# GEN_CART_EPROM_only.net
KiCad netlist of a schematic drawn in EAGLE
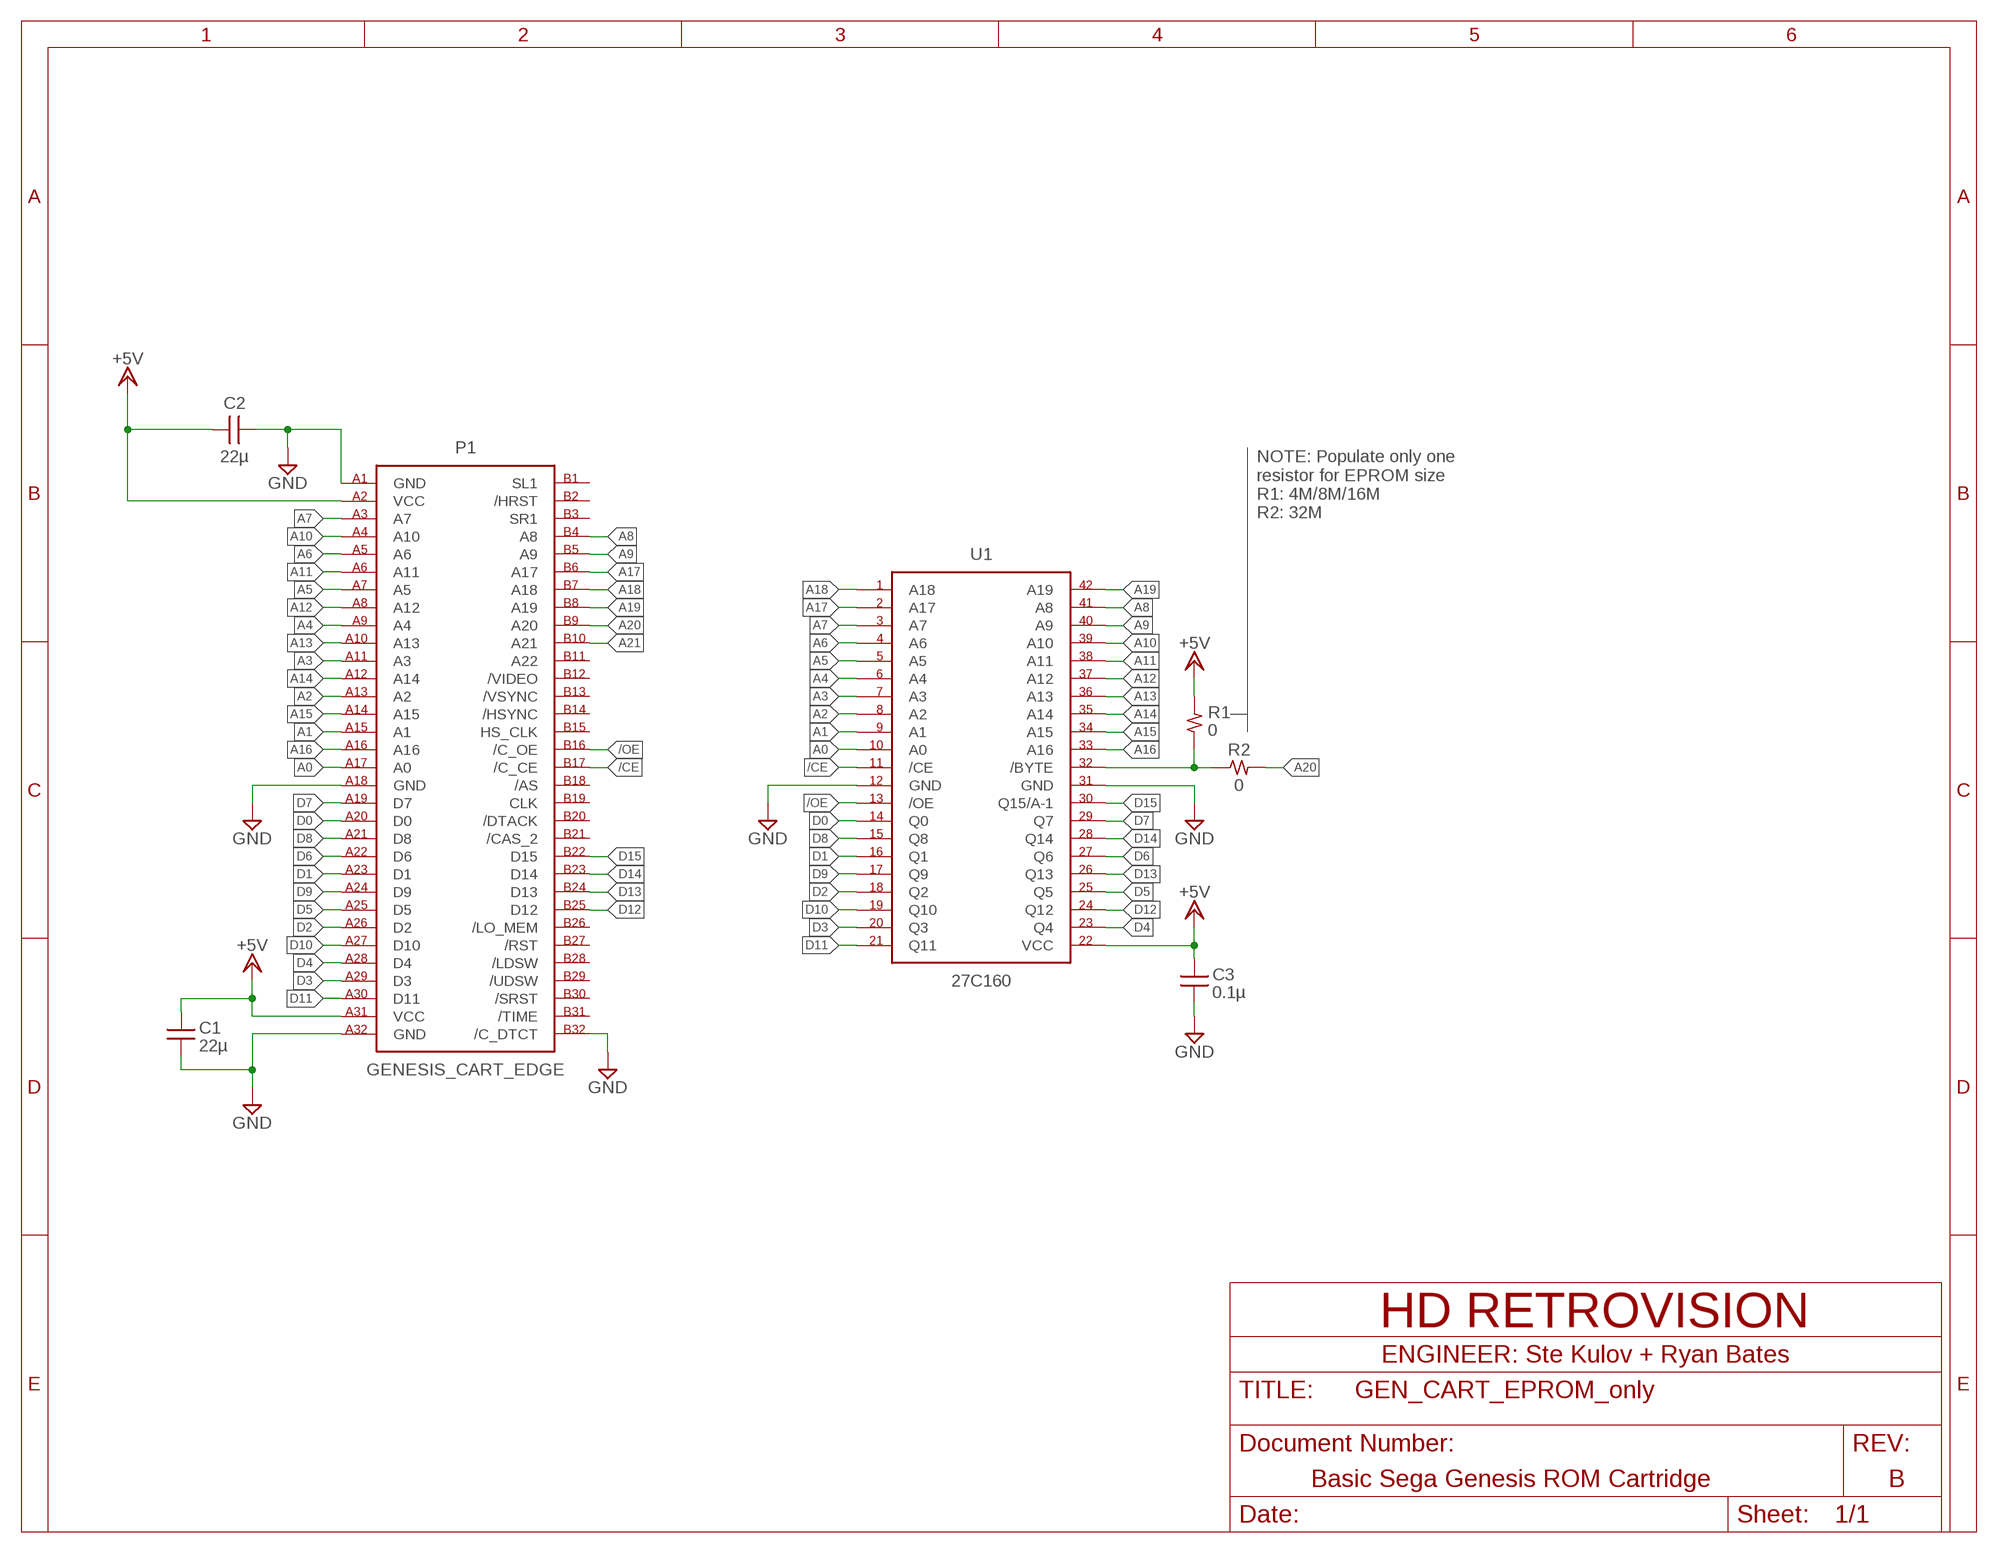
[diagram p0: schematic, sheet 1]

(export (version "E")
  (design (tool "Eeschema 10.0.6"))
  (components
    (comp (ref "C1")
      (value "22µ")
      (footprint "eagle-import:CAP_SMD1210")
      (libsource (lib "eagle-import") (part "CAP_SMD1210"))
    )
    (comp (ref "C2")
      (value "22µ")
      (footprint "eagle-import:CAP_SMD1210")
      (libsource (lib "eagle-import") (part "CAP_SMD_HORIZONTAL1210"))
    )
    (comp (ref "C3")
      (value "0.1µ")
      (footprint "eagle-import:CAP_SMD1210")
      (libsource (lib "eagle-import") (part "CAP_SMD1210"))
    )
    (comp (ref "P1")
      (value "GENESIS_CART_EDGE")
      (footprint "eagle-import:GENESIS_CART_EDGE")
      (libsource (lib "eagle-import") (part "GENESIS_CART_EDGE"))
    )
    (comp (ref "R1")
      (value "0")
      (footprint "eagle-import:RES_SMD0603")
      (libsource (lib "eagle-import") (part "RES_SMD0603"))
    )
    (comp (ref "R2")
      (value "0")
      (footprint "eagle-import:RES_SMD0603")
      (libsource (lib "eagle-import") (part "RES_SMD_HORIZONTAL0603"))
    )
    (comp (ref "U1")
      (value "27C160")
      (footprint "eagle-import:DIP_600MIL_42")
      (libsource (lib "eagle-import") (part "27C160"))
    )
  )
  (nets
    (net (code "1") (name "+5V") (class "Default")
      (node (ref "C1") (pin "P$2") (pinfunction "P$2_P$2") (pintype "passive"))
      (node (ref "C2") (pin "P$2") (pinfunction "P$2_P$2") (pintype "passive"))
      (node (ref "C3") (pin "P$2") (pinfunction "P$2_P$2") (pintype "passive"))
      (node (ref "P1") (pin "A2") (pinfunction "VCC_A2") (pintype "power_in"))
      (node (ref "P1") (pin "A31") (pinfunction "VCC_A31") (pintype "power_in"))
      (node (ref "R1") (pin "P$2") (pinfunction "2_P$2") (pintype "passive"))
      (node (ref "U1") (pin "P$22") (pinfunction "VCC_P$22") (pintype "power_in"))
    )
    (net (code "2") (name "A0") (class "Default")
      (node (ref "P1") (pin "A17") (pinfunction "A0_A17") (pintype "input"))
      (node (ref "U1") (pin "P$10") (pinfunction "A0_P$10") (pintype "input"))
    )
    (net (code "3") (name "A1") (class "Default")
      (node (ref "P1") (pin "A15") (pinfunction "A1_A15") (pintype "input"))
      (node (ref "U1") (pin "P$9") (pinfunction "A1_P$9") (pintype "input"))
    )
    (net (code "4") (name "A2") (class "Default")
      (node (ref "P1") (pin "A13") (pinfunction "A2_A13") (pintype "input"))
      (node (ref "U1") (pin "P$8") (pinfunction "A2_P$8") (pintype "input"))
    )
    (net (code "5") (name "A3") (class "Default")
      (node (ref "P1") (pin "A11") (pinfunction "A3_A11") (pintype "input"))
      (node (ref "U1") (pin "P$7") (pinfunction "A3_P$7") (pintype "input"))
    )
    (net (code "6") (name "A4") (class "Default")
      (node (ref "P1") (pin "A9") (pinfunction "A4_A9") (pintype "input"))
      (node (ref "U1") (pin "P$6") (pinfunction "A4_P$6") (pintype "input"))
    )
    (net (code "7") (name "A5") (class "Default")
      (node (ref "P1") (pin "A7") (pinfunction "A5_A7") (pintype "input"))
      (node (ref "U1") (pin "P$5") (pinfunction "A5_P$5") (pintype "input"))
    )
    (net (code "8") (name "A6") (class "Default")
      (node (ref "P1") (pin "A5") (pinfunction "A6_A5") (pintype "input"))
      (node (ref "U1") (pin "P$4") (pinfunction "A6_P$4") (pintype "input"))
    )
    (net (code "9") (name "A7") (class "Default")
      (node (ref "P1") (pin "A3") (pinfunction "A7_A3") (pintype "input"))
      (node (ref "U1") (pin "P$3") (pinfunction "A7_P$3") (pintype "input"))
    )
    (net (code "10") (name "A8") (class "Default")
      (node (ref "P1") (pin "B4") (pinfunction "A8_B4") (pintype "input"))
      (node (ref "U1") (pin "P$41") (pinfunction "A8_P$41") (pintype "input"))
    )
    (net (code "11") (name "A9") (class "Default")
      (node (ref "P1") (pin "B5") (pinfunction "A9_B5") (pintype "input"))
      (node (ref "U1") (pin "P$40") (pinfunction "A9_P$40") (pintype "input"))
    )
    (net (code "12") (name "A10") (class "Default")
      (node (ref "P1") (pin "A4") (pinfunction "A10_A4") (pintype "input"))
      (node (ref "U1") (pin "P$39") (pinfunction "A10_P$39") (pintype "input"))
    )
    (net (code "13") (name "A11") (class "Default")
      (node (ref "P1") (pin "A6") (pinfunction "A11_A6") (pintype "input"))
      (node (ref "U1") (pin "P$38") (pinfunction "A11_P$38") (pintype "input"))
    )
    (net (code "14") (name "A12") (class "Default")
      (node (ref "P1") (pin "A8") (pinfunction "A12_A8") (pintype "input"))
      (node (ref "U1") (pin "P$37") (pinfunction "A12_P$37") (pintype "input"))
    )
    (net (code "15") (name "A13") (class "Default")
      (node (ref "P1") (pin "A10") (pinfunction "A13_A10") (pintype "input"))
      (node (ref "U1") (pin "P$36") (pinfunction "A13_P$36") (pintype "input"))
    )
    (net (code "16") (name "A14") (class "Default")
      (node (ref "P1") (pin "A12") (pinfunction "A14_A12") (pintype "input"))
      (node (ref "U1") (pin "P$35") (pinfunction "A14_P$35") (pintype "input"))
    )
    (net (code "17") (name "A15") (class "Default")
      (node (ref "P1") (pin "A14") (pinfunction "A15_A14") (pintype "input"))
      (node (ref "U1") (pin "P$34") (pinfunction "A15_P$34") (pintype "input"))
    )
    (net (code "18") (name "A16") (class "Default")
      (node (ref "P1") (pin "A16") (pinfunction "A16_A16") (pintype "input"))
      (node (ref "U1") (pin "P$33") (pinfunction "A16_P$33") (pintype "input"))
    )
    (net (code "19") (name "A17") (class "Default")
      (node (ref "P1") (pin "B6") (pinfunction "A17_B6") (pintype "input"))
      (node (ref "U1") (pin "P$2") (pinfunction "A17_P$2") (pintype "input"))
    )
    (net (code "20") (name "A18") (class "Default")
      (node (ref "P1") (pin "B7") (pinfunction "A18_B7") (pintype "input"))
      (node (ref "U1") (pin "P$1") (pinfunction "A18_P$1") (pintype "input"))
    )
    (net (code "21") (name "A19") (class "Default")
      (node (ref "P1") (pin "B8") (pinfunction "A19_B8") (pintype "input"))
      (node (ref "U1") (pin "P$42") (pinfunction "A19_P$42") (pintype "input"))
    )
    (net (code "22") (name "A20") (class "Default")
      (node (ref "P1") (pin "B9") (pinfunction "A20_B9") (pintype "input"))
      (node (ref "R2") (pin "P$2") (pinfunction "2_P$2") (pintype "passive"))
    )
    (net (code "23") (name "A21") (class "Default")
      (node (ref "P1") (pin "B10") (pinfunction "A21_B10") (pintype "input"))
    )
    (net (code "24") (name "D0") (class "Default")
      (node (ref "P1") (pin "A20") (pinfunction "D0_A20") (pintype "bidirectional"))
      (node (ref "U1") (pin "P$14") (pinfunction "Q0_P$14") (pintype "output"))
    )
    (net (code "25") (name "D1") (class "Default")
      (node (ref "P1") (pin "A23") (pinfunction "D1_A23") (pintype "bidirectional"))
      (node (ref "U1") (pin "P$16") (pinfunction "Q1_P$16") (pintype "output"))
    )
    (net (code "26") (name "D2") (class "Default")
      (node (ref "P1") (pin "A26") (pinfunction "D2_A26") (pintype "bidirectional"))
      (node (ref "U1") (pin "P$18") (pinfunction "Q2_P$18") (pintype "output"))
    )
    (net (code "27") (name "D3") (class "Default")
      (node (ref "P1") (pin "A29") (pinfunction "D3_A29") (pintype "bidirectional"))
      (node (ref "U1") (pin "P$20") (pinfunction "Q3_P$20") (pintype "output"))
    )
    (net (code "28") (name "D4") (class "Default")
      (node (ref "P1") (pin "A28") (pinfunction "D4_A28") (pintype "bidirectional"))
      (node (ref "U1") (pin "P$23") (pinfunction "Q4_P$23") (pintype "output"))
    )
    (net (code "29") (name "D5") (class "Default")
      (node (ref "P1") (pin "A25") (pinfunction "D5_A25") (pintype "bidirectional"))
      (node (ref "U1") (pin "P$25") (pinfunction "Q5_P$25") (pintype "output"))
    )
    (net (code "30") (name "D6") (class "Default")
      (node (ref "P1") (pin "A22") (pinfunction "D6_A22") (pintype "bidirectional"))
      (node (ref "U1") (pin "P$27") (pinfunction "Q6_P$27") (pintype "output"))
    )
    (net (code "31") (name "D7") (class "Default")
      (node (ref "P1") (pin "A19") (pinfunction "D7_A19") (pintype "bidirectional"))
      (node (ref "U1") (pin "P$29") (pinfunction "Q7_P$29") (pintype "output"))
    )
    (net (code "32") (name "D8") (class "Default")
      (node (ref "P1") (pin "A21") (pinfunction "D8_A21") (pintype "bidirectional"))
      (node (ref "U1") (pin "P$15") (pinfunction "Q8_P$15") (pintype "output"))
    )
    (net (code "33") (name "D9") (class "Default")
      (node (ref "P1") (pin "A24") (pinfunction "D9_A24") (pintype "bidirectional"))
      (node (ref "U1") (pin "P$17") (pinfunction "Q9_P$17") (pintype "output"))
    )
    (net (code "34") (name "D10") (class "Default")
      (node (ref "P1") (pin "A27") (pinfunction "D10_A27") (pintype "bidirectional"))
      (node (ref "U1") (pin "P$19") (pinfunction "Q10_P$19") (pintype "output"))
    )
    (net (code "35") (name "D11") (class "Default")
      (node (ref "P1") (pin "A30") (pinfunction "D11_A30") (pintype "bidirectional"))
      (node (ref "U1") (pin "P$21") (pinfunction "Q11_P$21") (pintype "output"))
    )
    (net (code "36") (name "D12") (class "Default")
      (node (ref "P1") (pin "B25") (pinfunction "D12_B25") (pintype "bidirectional"))
      (node (ref "U1") (pin "P$24") (pinfunction "Q12_P$24") (pintype "output"))
    )
    (net (code "37") (name "D13") (class "Default")
      (node (ref "P1") (pin "B24") (pinfunction "D13_B24") (pintype "bidirectional"))
      (node (ref "U1") (pin "P$26") (pinfunction "Q13_P$26") (pintype "output"))
    )
    (net (code "38") (name "D14") (class "Default")
      (node (ref "P1") (pin "B23") (pinfunction "D14_B23") (pintype "bidirectional"))
      (node (ref "U1") (pin "P$28") (pinfunction "Q14_P$28") (pintype "output"))
    )
    (net (code "39") (name "D15") (class "Default")
      (node (ref "P1") (pin "B22") (pinfunction "D15_B22") (pintype "bidirectional"))
      (node (ref "U1") (pin "P$30") (pinfunction "Q15/A-1_P$30") (pintype "bidirectional"))
    )
    (net (code "40") (name "GND") (class "Default")
      (node (ref "C1") (pin "P$1") (pinfunction "P$1_P$1") (pintype "passive"))
      (node (ref "C2") (pin "P$1") (pinfunction "P$1_P$1") (pintype "passive"))
      (node (ref "C3") (pin "P$1") (pinfunction "P$1_P$1") (pintype "passive"))
      (node (ref "P1") (pin "A1") (pinfunction "GND_A1") (pintype "power_in"))
      (node (ref "P1") (pin "A18") (pinfunction "GND_A18") (pintype "power_in"))
      (node (ref "P1") (pin "A32") (pinfunction "GND_A32") (pintype "power_in"))
      (node (ref "P1") (pin "B32") (pinfunction "/C_DTCT_B32") (pintype "output"))
      (node (ref "U1") (pin "P$12") (pinfunction "GND_P$12") (pintype "power_in"))
      (node (ref "U1") (pin "P$31") (pinfunction "GND_P$31") (pintype "power_in"))
    )
    (net (code "41") (name "Net-(R1-1)") (class "Default")
      (node (ref "R1") (pin "P$1") (pinfunction "1_P$1") (pintype "passive"))
      (node (ref "R2") (pin "P$1") (pinfunction "1_P$1") (pintype "passive"))
      (node (ref "U1") (pin "P$32") (pinfunction "/BYTE_P$32") (pintype "input"))
    )
    (net (code "42") (name "unconnected-(P1-A22-PadB11)") (class "Default")
      (node (ref "P1") (pin "B11") (pinfunction "A22_B11") (pintype "input"))
    )
    (net (code "43") (name "unconnected-(P1-CLK-PadB19)") (class "Default")
      (node (ref "P1") (pin "B19") (pinfunction "CLK_B19") (pintype "input"))
    )
    (net (code "44") (name "unconnected-(P1-HS_CLK-PadB15)") (class "Default")
      (node (ref "P1") (pin "B15") (pinfunction "HS_CLK_B15") (pintype "input"))
    )
    (net (code "45") (name "unconnected-(P1-SL1-PadB1)") (class "Default")
      (node (ref "P1") (pin "B1") (pinfunction "SL1_B1") (pintype "input"))
    )
    (net (code "46") (name "unconnected-(P1-SR1-PadB3)") (class "Default")
      (node (ref "P1") (pin "B3") (pinfunction "SR1_B3") (pintype "input"))
    )
    (net (code "47") (name "unconnected-(P1-{slash}AS-PadB18)") (class "Default")
      (node (ref "P1") (pin "B18") (pinfunction "/AS_B18") (pintype "input"))
    )
    (net (code "48") (name "unconnected-(P1-{slash}CAS_2-PadB21)") (class "Default")
      (node (ref "P1") (pin "B21") (pinfunction "/CAS_2_B21") (pintype "input"))
    )
    (net (code "49") (name "unconnected-(P1-{slash}DTACK-PadB20)") (class "Default")
      (node (ref "P1") (pin "B20") (pinfunction "/DTACK_B20") (pintype "output"))
    )
    (net (code "50") (name "unconnected-(P1-{slash}HRST-PadB2)") (class "Default")
      (node (ref "P1") (pin "B2") (pinfunction "/HRST_B2") (pintype "output"))
    )
    (net (code "51") (name "unconnected-(P1-{slash}HSYNC-PadB14)") (class "Default")
      (node (ref "P1") (pin "B14") (pinfunction "/HSYNC_B14") (pintype "input"))
    )
    (net (code "52") (name "unconnected-(P1-{slash}LDSW-PadB28)") (class "Default")
      (node (ref "P1") (pin "B28") (pinfunction "/LDSW_B28") (pintype "input"))
    )
    (net (code "53") (name "unconnected-(P1-{slash}LO_MEM-PadB26)") (class "Default")
      (node (ref "P1") (pin "B26") (pinfunction "/LO_MEM_B26") (pintype "input"))
    )
    (net (code "54") (name "unconnected-(P1-{slash}RST-PadB27)") (class "Default")
      (node (ref "P1") (pin "B27") (pinfunction "/RST_B27") (pintype "input"))
    )
    (net (code "55") (name "unconnected-(P1-{slash}SRST-PadB30)") (class "Default")
      (node (ref "P1") (pin "B30") (pinfunction "/SRST_B30") (pintype "output"))
    )
    (net (code "56") (name "unconnected-(P1-{slash}TIME-PadB31)") (class "Default")
      (node (ref "P1") (pin "B31") (pinfunction "/TIME_B31") (pintype "input"))
    )
    (net (code "57") (name "unconnected-(P1-{slash}UDSW-PadB29)") (class "Default")
      (node (ref "P1") (pin "B29") (pinfunction "/UDSW_B29") (pintype "input"))
    )
    (net (code "58") (name "unconnected-(P1-{slash}VIDEO-PadB12)") (class "Default")
      (node (ref "P1") (pin "B12") (pinfunction "/VIDEO_B12") (pintype "input"))
    )
    (net (code "59") (name "unconnected-(P1-{slash}VSYNC-PadB13)") (class "Default")
      (node (ref "P1") (pin "B13") (pinfunction "/VSYNC_B13") (pintype "input"))
    )
    (net (code "60") (name "{slash}CE") (class "Default")
      (node (ref "P1") (pin "B17") (pinfunction "/C_CE_B17") (pintype "input"))
      (node (ref "U1") (pin "P$11") (pinfunction "/CE_P$11") (pintype "input"))
    )
    (net (code "61") (name "{slash}OE") (class "Default")
      (node (ref "P1") (pin "B16") (pinfunction "/C_OE_B16") (pintype "input"))
      (node (ref "U1") (pin "P$13") (pinfunction "/OE_P$13") (pintype "input"))
    )
  )
)
